# USER.net
KiCad netlist of a schematic drawn in EAGLE
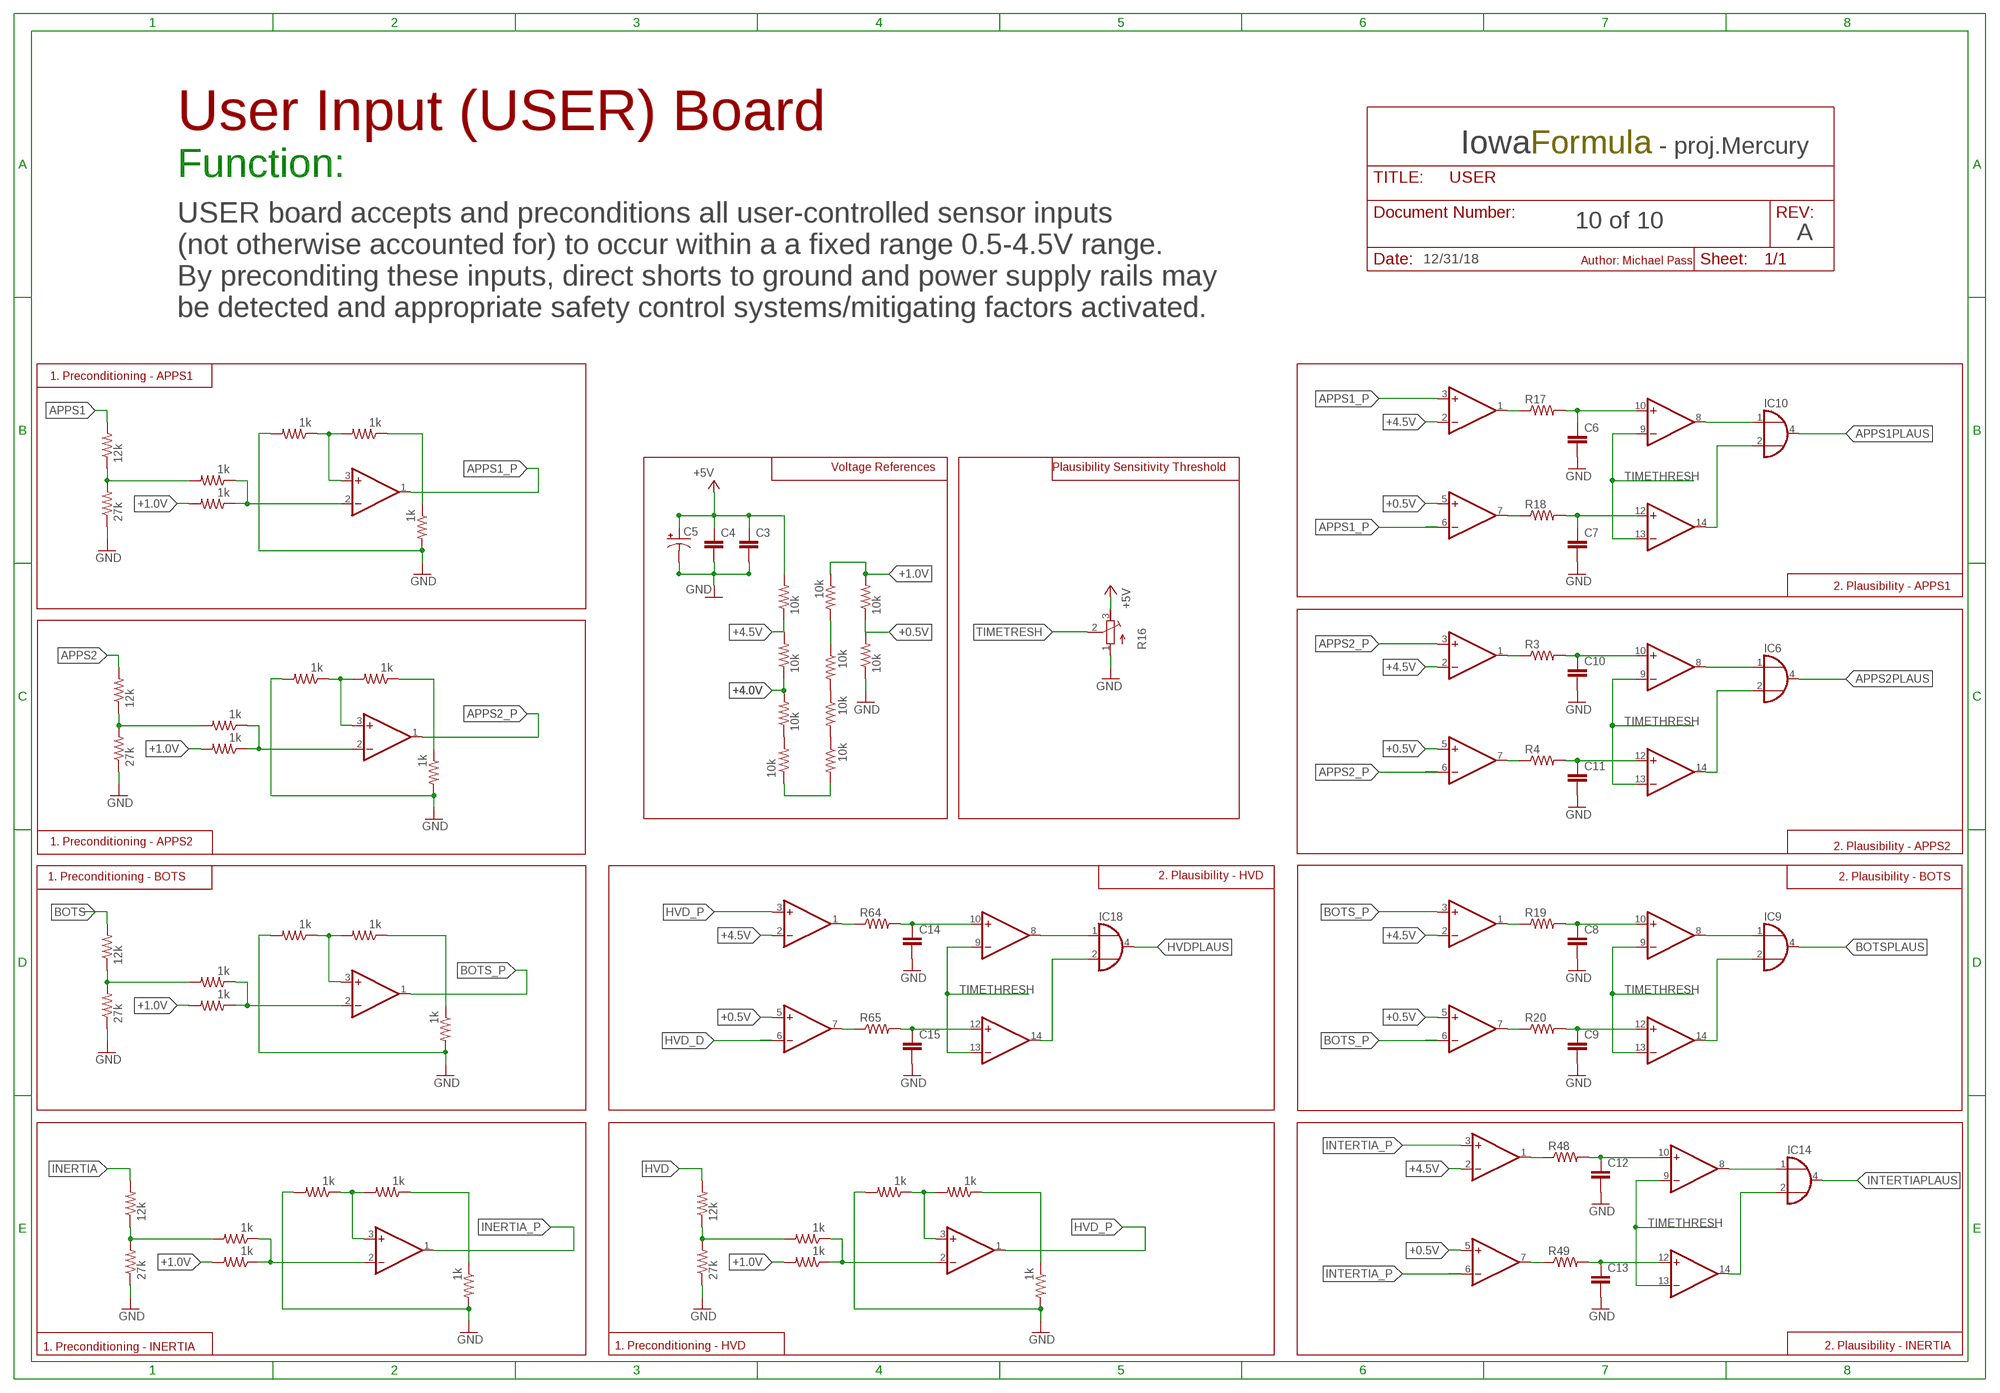
[diagram p0: schematic, sheet 1]

(export (version "E")
  (design (tool "Eeschema 10.0.6"))
  (components
    (comp (ref "C3")
      (value "C-EUC0805")
      (footprint "eagle-import:C0805")
      (libsource (lib "eagle-import") (part "C-EUC0805"))
    )
    (comp (ref "C4")
      (value "C-EUC0805")
      (footprint "eagle-import:C0805")
      (libsource (lib "eagle-import") (part "C-EUC0805"))
    )
    (comp (ref "C5")
      (value "CPOL-US085CS-1AR")
      (footprint "eagle-import:085CS_1AR")
      (libsource (lib "eagle-import") (part "CPOL-US085CS-1AR"))
    )
    (comp (ref "C6")
      (value "C-EUC0805")
      (footprint "eagle-import:C0805")
      (libsource (lib "eagle-import") (part "C-EUC0805"))
    )
    (comp (ref "C7")
      (value "C-EUC0805")
      (footprint "eagle-import:C0805")
      (libsource (lib "eagle-import") (part "C-EUC0805"))
    )
    (comp (ref "C8")
      (value "C-EUC0805")
      (footprint "eagle-import:C0805")
      (libsource (lib "eagle-import") (part "C-EUC0805"))
    )
    (comp (ref "C9")
      (value "C-EUC0805")
      (footprint "eagle-import:C0805")
      (libsource (lib "eagle-import") (part "C-EUC0805"))
    )
    (comp (ref "C10")
      (value "C-EUC0805")
      (footprint "eagle-import:C0805")
      (libsource (lib "eagle-import") (part "C-EUC0805"))
    )
    (comp (ref "C11")
      (value "C-EUC0805")
      (footprint "eagle-import:C0805")
      (libsource (lib "eagle-import") (part "C-EUC0805"))
    )
    (comp (ref "C12")
      (value "C-EUC0805")
      (footprint "eagle-import:C0805")
      (libsource (lib "eagle-import") (part "C-EUC0805"))
    )
    (comp (ref "C13")
      (value "C-EUC0805")
      (footprint "eagle-import:C0805")
      (libsource (lib "eagle-import") (part "C-EUC0805"))
    )
    (comp (ref "C14")
      (value "C-EUC0805")
      (footprint "eagle-import:C0805")
      (libsource (lib "eagle-import") (part "C-EUC0805"))
    )
    (comp (ref "C15")
      (value "C-EUC0805")
      (footprint "eagle-import:C0805")
      (libsource (lib "eagle-import") (part "C-EUC0805"))
    )
    (comp (ref "IC1")
      (value "OP11D")
      (footprint "eagle-import:SO14")
      (libsource (lib "eagle-import") (part "OP11D"))
    )
    (comp (ref "IC3")
      (value "OP11D")
      (footprint "eagle-import:SO14")
      (libsource (lib "eagle-import") (part "OP11D"))
    )
    (comp (ref "IC4")
      (value "OP11D")
      (footprint "eagle-import:SO14")
      (libsource (lib "eagle-import") (part "OP11D"))
    )
    (comp (ref "IC5")
      (value "OP11D")
      (footprint "eagle-import:SO14")
      (libsource (lib "eagle-import") (part "OP11D"))
    )
    (comp (ref "IC6")
      (value "74AHC1G32DCK")
      (footprint "eagle-import:SC70-5")
      (libsource (lib "eagle-import") (part "741G32DCKAHC"))
    )
    (comp (ref "IC7")
      (value "OP11D")
      (footprint "eagle-import:SO14")
      (libsource (lib "eagle-import") (part "OP11D"))
    )
    (comp (ref "IC8")
      (value "OP11D")
      (footprint "eagle-import:SO14")
      (libsource (lib "eagle-import") (part "OP11D"))
    )
    (comp (ref "IC9")
      (value "74AHC1G32DCK")
      (footprint "eagle-import:SC70-5")
      (libsource (lib "eagle-import") (part "741G32DCKAHC"))
    )
    (comp (ref "IC10")
      (value "74AHC1G32DCK")
      (footprint "eagle-import:SC70-5")
      (libsource (lib "eagle-import") (part "741G32DCKAHC"))
    )
    (comp (ref "IC13")
      (value "OP11D")
      (footprint "eagle-import:SO14")
      (libsource (lib "eagle-import") (part "OP11D"))
    )
    (comp (ref "IC14")
      (value "74AHC1G32DCK")
      (footprint "eagle-import:SC70-5")
      (libsource (lib "eagle-import") (part "741G32DCKAHC"))
    )
    (comp (ref "IC17")
      (value "OP11D")
      (footprint "eagle-import:SO14")
      (libsource (lib "eagle-import") (part "OP11D"))
    )
    (comp (ref "IC18")
      (value "74AHC1G32DCK")
      (footprint "eagle-import:SC70-5")
      (libsource (lib "eagle-import") (part "741G32DCKAHC"))
    )
    (comp (ref "IC19")
      (value "OP11D")
      (footprint "eagle-import:SO14")
      (libsource (lib "eagle-import") (part "OP11D"))
    )
    (comp (ref "IC20")
      (value "OP11D")
      (footprint "eagle-import:SO14")
      (libsource (lib "eagle-import") (part "OP11D"))
    )
    (comp (ref "R1")
      (value "12k")
      (footprint "eagle-import:R0805")
      (libsource (lib "eagle-import") (part "R-US_R0805"))
    )
    (comp (ref "R2")
      (value "27k")
      (footprint "eagle-import:R0805")
      (libsource (lib "eagle-import") (part "R-US_R0805"))
    )
    (comp (ref "R3")
      (value "R-US_R0805")
      (footprint "eagle-import:R0805")
      (libsource (lib "eagle-import") (part "R-US_R0805"))
    )
    (comp (ref "R4")
      (value "R-US_R0805")
      (footprint "eagle-import:R0805")
      (libsource (lib "eagle-import") (part "R-US_R0805"))
    )
    (comp (ref "R5")
      (value "10k")
      (footprint "eagle-import:R0805")
      (libsource (lib "eagle-import") (part "R-US_R0805"))
    )
    (comp (ref "R6")
      (value "10k")
      (footprint "eagle-import:R0805")
      (libsource (lib "eagle-import") (part "R-US_R0805"))
    )
    (comp (ref "R7")
      (value "12k")
      (footprint "eagle-import:R0805")
      (libsource (lib "eagle-import") (part "R-US_R0805"))
    )
    (comp (ref "R8")
      (value "10k")
      (footprint "eagle-import:R0805")
      (libsource (lib "eagle-import") (part "R-US_R0805"))
    )
    (comp (ref "R9")
      (value "10k")
      (footprint "eagle-import:R0805")
      (libsource (lib "eagle-import") (part "R-US_R0805"))
    )
    (comp (ref "R10")
      (value "10k")
      (footprint "eagle-import:R0805")
      (libsource (lib "eagle-import") (part "R-US_R0805"))
    )
    (comp (ref "R11")
      (value "10k")
      (footprint "eagle-import:R0805")
      (libsource (lib "eagle-import") (part "R-US_R0805"))
    )
    (comp (ref "R12")
      (value "10k")
      (footprint "eagle-import:R0805")
      (libsource (lib "eagle-import") (part "R-US_R0805"))
    )
    (comp (ref "R13")
      (value "10k")
      (footprint "eagle-import:R0805")
      (libsource (lib "eagle-import") (part "R-US_R0805"))
    )
    (comp (ref "R14")
      (value "10k")
      (footprint "eagle-import:R0805")
      (libsource (lib "eagle-import") (part "R-US_R0805"))
    )
    (comp (ref "R15")
      (value "10k")
      (footprint "eagle-import:R0805")
      (libsource (lib "eagle-import") (part "R-US_R0805"))
    )
    (comp (ref "R16")
      (value "R-TRIMM3224X")
      (footprint "eagle-import:RTRIM3224X")
      (libsource (lib "eagle-import") (part "R-TRIMM3224X"))
    )
    (comp (ref "R17")
      (value "R-US_R0805")
      (footprint "eagle-import:R0805")
      (libsource (lib "eagle-import") (part "R-US_R0805"))
    )
    (comp (ref "R18")
      (value "R-US_R0805")
      (footprint "eagle-import:R0805")
      (libsource (lib "eagle-import") (part "R-US_R0805"))
    )
    (comp (ref "R19")
      (value "R-US_R0805")
      (footprint "eagle-import:R0805")
      (libsource (lib "eagle-import") (part "R-US_R0805"))
    )
    (comp (ref "R20")
      (value "R-US_R0805")
      (footprint "eagle-import:R0805")
      (libsource (lib "eagle-import") (part "R-US_R0805"))
    )
    (comp (ref "R21")
      (value "27k")
      (footprint "eagle-import:R0805")
      (libsource (lib "eagle-import") (part "R-US_R0805"))
    )
    (comp (ref "R22")
      (value "1k")
      (footprint "eagle-import:R0805")
      (libsource (lib "eagle-import") (part "R-US_R0805"))
    )
    (comp (ref "R23")
      (value "1k")
      (footprint "eagle-import:R0805")
      (libsource (lib "eagle-import") (part "R-US_R0805"))
    )
    (comp (ref "R24")
      (value "1k")
      (footprint "eagle-import:R0805")
      (libsource (lib "eagle-import") (part "R-US_R0805"))
    )
    (comp (ref "R25")
      (value "1k")
      (footprint "eagle-import:R0805")
      (libsource (lib "eagle-import") (part "R-US_R0805"))
    )
    (comp (ref "R26")
      (value "1k")
      (footprint "eagle-import:R0805")
      (libsource (lib "eagle-import") (part "R-US_R0805"))
    )
    (comp (ref "R48")
      (value "R-US_R0805")
      (footprint "eagle-import:R0805")
      (libsource (lib "eagle-import") (part "R-US_R0805"))
    )
    (comp (ref "R49")
      (value "R-US_R0805")
      (footprint "eagle-import:R0805")
      (libsource (lib "eagle-import") (part "R-US_R0805"))
    )
    (comp (ref "R64")
      (value "R-US_R0805")
      (footprint "eagle-import:R0805")
      (libsource (lib "eagle-import") (part "R-US_R0805"))
    )
    (comp (ref "R65")
      (value "R-US_R0805")
      (footprint "eagle-import:R0805")
      (libsource (lib "eagle-import") (part "R-US_R0805"))
    )
    (comp (ref "R66")
      (value "1k")
      (footprint "eagle-import:R0805")
      (libsource (lib "eagle-import") (part "R-US_R0805"))
    )
    (comp (ref "R67")
      (value "1k")
      (footprint "eagle-import:R0805")
      (libsource (lib "eagle-import") (part "R-US_R0805"))
    )
    (comp (ref "R68")
      (value "1k")
      (footprint "eagle-import:R0805")
      (libsource (lib "eagle-import") (part "R-US_R0805"))
    )
    (comp (ref "R69")
      (value "1k")
      (footprint "eagle-import:R0805")
      (libsource (lib "eagle-import") (part "R-US_R0805"))
    )
    (comp (ref "R70")
      (value "1k")
      (footprint "eagle-import:R0805")
      (libsource (lib "eagle-import") (part "R-US_R0805"))
    )
    (comp (ref "R71")
      (value "12k")
      (footprint "eagle-import:R0805")
      (libsource (lib "eagle-import") (part "R-US_R0805"))
    )
    (comp (ref "R72")
      (value "27k")
      (footprint "eagle-import:R0805")
      (libsource (lib "eagle-import") (part "R-US_R0805"))
    )
    (comp (ref "R73")
      (value "1k")
      (footprint "eagle-import:R0805")
      (libsource (lib "eagle-import") (part "R-US_R0805"))
    )
    (comp (ref "R74")
      (value "1k")
      (footprint "eagle-import:R0805")
      (libsource (lib "eagle-import") (part "R-US_R0805"))
    )
    (comp (ref "R75")
      (value "1k")
      (footprint "eagle-import:R0805")
      (libsource (lib "eagle-import") (part "R-US_R0805"))
    )
    (comp (ref "R76")
      (value "1k")
      (footprint "eagle-import:R0805")
      (libsource (lib "eagle-import") (part "R-US_R0805"))
    )
    (comp (ref "R77")
      (value "1k")
      (footprint "eagle-import:R0805")
      (libsource (lib "eagle-import") (part "R-US_R0805"))
    )
    (comp (ref "R78")
      (value "12k")
      (footprint "eagle-import:R0805")
      (libsource (lib "eagle-import") (part "R-US_R0805"))
    )
    (comp (ref "R79")
      (value "27k")
      (footprint "eagle-import:R0805")
      (libsource (lib "eagle-import") (part "R-US_R0805"))
    )
    (comp (ref "R80")
      (value "1k")
      (footprint "eagle-import:R0805")
      (libsource (lib "eagle-import") (part "R-US_R0805"))
    )
    (comp (ref "R81")
      (value "1k")
      (footprint "eagle-import:R0805")
      (libsource (lib "eagle-import") (part "R-US_R0805"))
    )
    (comp (ref "R82")
      (value "1k")
      (footprint "eagle-import:R0805")
      (libsource (lib "eagle-import") (part "R-US_R0805"))
    )
    (comp (ref "R83")
      (value "1k")
      (footprint "eagle-import:R0805")
      (libsource (lib "eagle-import") (part "R-US_R0805"))
    )
    (comp (ref "R84")
      (value "1k")
      (footprint "eagle-import:R0805")
      (libsource (lib "eagle-import") (part "R-US_R0805"))
    )
    (comp (ref "R85")
      (value "12k")
      (footprint "eagle-import:R0805")
      (libsource (lib "eagle-import") (part "R-US_R0805"))
    )
    (comp (ref "R86")
      (value "27k")
      (footprint "eagle-import:R0805")
      (libsource (lib "eagle-import") (part "R-US_R0805"))
    )
    (comp (ref "R87")
      (value "1k")
      (footprint "eagle-import:R0805")
      (libsource (lib "eagle-import") (part "R-US_R0805"))
    )
    (comp (ref "R88")
      (value "1k")
      (footprint "eagle-import:R0805")
      (libsource (lib "eagle-import") (part "R-US_R0805"))
    )
    (comp (ref "R89")
      (value "1k")
      (footprint "eagle-import:R0805")
      (libsource (lib "eagle-import") (part "R-US_R0805"))
    )
    (comp (ref "R90")
      (value "1k")
      (footprint "eagle-import:R0805")
      (libsource (lib "eagle-import") (part "R-US_R0805"))
    )
    (comp (ref "R91")
      (value "1k")
      (footprint "eagle-import:R0805")
      (libsource (lib "eagle-import") (part "R-US_R0805"))
    )
  )
  (nets
    (net (code "1") (name "+0.5V") (class "Default")
      (node (ref "IC1") (pin "5") (pinfunction "+IN_5") (pintype "input"))
      (node (ref "IC13") (pin "5") (pinfunction "+IN_5") (pintype "input"))
      (node (ref "IC17") (pin "5") (pinfunction "+IN_5") (pintype "input"))
      (node (ref "IC4") (pin "5") (pinfunction "+IN_5") (pintype "input"))
      (node (ref "IC5") (pin "5") (pinfunction "+IN_5") (pintype "input"))
      (node (ref "R14") (pin "1") (pinfunction "1_1") (pintype "passive"))
      (node (ref "R15") (pin "2") (pinfunction "2_2") (pintype "passive"))
    )
    (net (code "2") (name "+1.0V") (class "Default")
      (node (ref "R13") (pin "1") (pinfunction "1_1") (pintype "passive"))
      (node (ref "R14") (pin "2") (pinfunction "2_2") (pintype "passive"))
      (node (ref "R23") (pin "2") (pinfunction "2_2") (pintype "passive"))
      (node (ref "R67") (pin "2") (pinfunction "2_2") (pintype "passive"))
      (node (ref "R74") (pin "2") (pinfunction "2_2") (pintype "passive"))
      (node (ref "R81") (pin "2") (pinfunction "2_2") (pintype "passive"))
      (node (ref "R88") (pin "2") (pinfunction "2_2") (pintype "passive"))
    )
    (net (code "3") (name "+4.0V") (class "Default")
      (node (ref "R6") (pin "1") (pinfunction "1_1") (pintype "passive"))
      (node (ref "R8") (pin "2") (pinfunction "2_2") (pintype "passive"))
    )
    (net (code "4") (name "+4.5V") (class "Default")
      (node (ref "IC1") (pin "2") (pinfunction "-IN_2") (pintype "input"))
      (node (ref "IC13") (pin "2") (pinfunction "-IN_2") (pintype "input"))
      (node (ref "IC17") (pin "2") (pinfunction "-IN_2") (pintype "input"))
      (node (ref "IC4") (pin "2") (pinfunction "-IN_2") (pintype "input"))
      (node (ref "IC5") (pin "2") (pinfunction "-IN_2") (pintype "input"))
      (node (ref "R5") (pin "1") (pinfunction "1_1") (pintype "passive"))
      (node (ref "R6") (pin "2") (pinfunction "2_2") (pintype "passive"))
    )
    (net (code "5") (name "+5V") (class "Default")
      (node (ref "C3") (pin "1") (pinfunction "1_1") (pintype "passive"))
      (node (ref "C4") (pin "1") (pinfunction "1_1") (pintype "passive"))
      (node (ref "C5") (pin "+") (pinfunction "+_+") (pintype "passive"))
      (node (ref "R16") (pin "3") (pinfunction "E_3") (pintype "passive"))
      (node (ref "R5") (pin "2") (pinfunction "2_2") (pintype "passive"))
    )
    (net (code "6") (name "/TIMETHRESH") (class "Default")
      (node (ref "IC1") (pin "13") (pinfunction "-IN_13") (pintype "input"))
      (node (ref "IC1") (pin "9") (pinfunction "-IN_9") (pintype "input"))
      (node (ref "IC13") (pin "13") (pinfunction "-IN_13") (pintype "input"))
      (node (ref "IC13") (pin "9") (pinfunction "-IN_9") (pintype "input"))
      (node (ref "IC17") (pin "13") (pinfunction "-IN_13") (pintype "input"))
      (node (ref "IC17") (pin "9") (pinfunction "-IN_9") (pintype "input"))
      (node (ref "IC4") (pin "13") (pinfunction "-IN_13") (pintype "input"))
      (node (ref "IC4") (pin "9") (pinfunction "-IN_9") (pintype "input"))
      (node (ref "IC5") (pin "13") (pinfunction "-IN_13") (pintype "input"))
      (node (ref "IC5") (pin "9") (pinfunction "-IN_9") (pintype "input"))
    )
    (net (code "7") (name "APPS1") (class "Default")
      (node (ref "R71") (pin "2") (pinfunction "2_2") (pintype "passive"))
    )
    (net (code "8") (name "APPS1PLAUS") (class "Default")
      (node (ref "IC10") (pin "4") (pinfunction "O_4") (pintype "output"))
    )
    (net (code "9") (name "APPS1_P") (class "Default")
      (node (ref "IC5") (pin "3") (pinfunction "+IN_3") (pintype "input"))
      (node (ref "IC5") (pin "6") (pinfunction "-IN_6") (pintype "input"))
      (node (ref "IC7") (pin "1") (pinfunction "OUT_1") (pintype "output"))
    )
    (net (code "10") (name "APPS2") (class "Default")
      (node (ref "R78") (pin "2") (pinfunction "2_2") (pintype "passive"))
    )
    (net (code "11") (name "APPS2PLAUS") (class "Default")
      (node (ref "IC6") (pin "4") (pinfunction "O_4") (pintype "output"))
    )
    (net (code "12") (name "APPS2_P") (class "Default")
      (node (ref "IC1") (pin "3") (pinfunction "+IN_3") (pintype "input"))
      (node (ref "IC1") (pin "6") (pinfunction "-IN_6") (pintype "input"))
      (node (ref "IC19") (pin "1") (pinfunction "OUT_1") (pintype "output"))
    )
    (net (code "13") (name "BOTS") (class "Default")
      (node (ref "R7") (pin "2") (pinfunction "2_2") (pintype "passive"))
    )
    (net (code "14") (name "BOTSPLAUS") (class "Default")
      (node (ref "IC9") (pin "4") (pinfunction "O_4") (pintype "output"))
    )
    (net (code "15") (name "BOTS_P") (class "Default")
      (node (ref "IC4") (pin "3") (pinfunction "+IN_3") (pintype "input"))
      (node (ref "IC4") (pin "6") (pinfunction "-IN_6") (pintype "input"))
      (node (ref "IC8") (pin "1") (pinfunction "OUT_1") (pintype "output"))
    )
    (net (code "16") (name "GND") (class "Default")
      (node (ref "C10") (pin "2") (pinfunction "2_2") (pintype "passive"))
      (node (ref "C11") (pin "2") (pinfunction "2_2") (pintype "passive"))
      (node (ref "C12") (pin "2") (pinfunction "2_2") (pintype "passive"))
      (node (ref "C13") (pin "2") (pinfunction "2_2") (pintype "passive"))
      (node (ref "C14") (pin "2") (pinfunction "2_2") (pintype "passive"))
      (node (ref "C15") (pin "2") (pinfunction "2_2") (pintype "passive"))
      (node (ref "C3") (pin "2") (pinfunction "2_2") (pintype "passive"))
      (node (ref "C4") (pin "2") (pinfunction "2_2") (pintype "passive"))
      (node (ref "C5") (pin "-") (pinfunction "-_-") (pintype "passive"))
      (node (ref "C6") (pin "2") (pinfunction "2_2") (pintype "passive"))
      (node (ref "C7") (pin "2") (pinfunction "2_2") (pintype "passive"))
      (node (ref "C8") (pin "2") (pinfunction "2_2") (pintype "passive"))
      (node (ref "C9") (pin "2") (pinfunction "2_2") (pintype "passive"))
      (node (ref "R15") (pin "1") (pinfunction "1_1") (pintype "passive"))
      (node (ref "R16") (pin "1") (pinfunction "A_1") (pintype "passive"))
      (node (ref "R2") (pin "1") (pinfunction "1_1") (pintype "passive"))
      (node (ref "R21") (pin "1") (pinfunction "1_1") (pintype "passive"))
      (node (ref "R24") (pin "2") (pinfunction "2_2") (pintype "passive"))
      (node (ref "R26") (pin "2") (pinfunction "2_2") (pintype "passive"))
      (node (ref "R68") (pin "2") (pinfunction "2_2") (pintype "passive"))
      (node (ref "R70") (pin "2") (pinfunction "2_2") (pintype "passive"))
      (node (ref "R72") (pin "1") (pinfunction "1_1") (pintype "passive"))
      (node (ref "R75") (pin "2") (pinfunction "2_2") (pintype "passive"))
      (node (ref "R77") (pin "2") (pinfunction "2_2") (pintype "passive"))
      (node (ref "R79") (pin "1") (pinfunction "1_1") (pintype "passive"))
      (node (ref "R82") (pin "2") (pinfunction "2_2") (pintype "passive"))
      (node (ref "R84") (pin "2") (pinfunction "2_2") (pintype "passive"))
      (node (ref "R86") (pin "1") (pinfunction "1_1") (pintype "passive"))
      (node (ref "R89") (pin "2") (pinfunction "2_2") (pintype "passive"))
      (node (ref "R91") (pin "2") (pinfunction "2_2") (pintype "passive"))
    )
    (net (code "17") (name "HVD") (class "Default")
      (node (ref "R85") (pin "2") (pinfunction "2_2") (pintype "passive"))
    )
    (net (code "18") (name "HVDPLAUS") (class "Default")
      (node (ref "IC18") (pin "4") (pinfunction "O_4") (pintype "output"))
    )
    (net (code "19") (name "HVD_D") (class "Default")
      (node (ref "IC17") (pin "6") (pinfunction "-IN_6") (pintype "input"))
    )
    (net (code "20") (name "HVD_P") (class "Default")
      (node (ref "IC17") (pin "3") (pinfunction "+IN_3") (pintype "input"))
      (node (ref "IC20") (pin "1") (pinfunction "OUT_1") (pintype "output"))
    )
    (net (code "21") (name "INERTIA") (class "Default")
      (node (ref "R1") (pin "2") (pinfunction "2_2") (pintype "passive"))
    )
    (net (code "22") (name "INERTIA_P") (class "Default")
      (node (ref "IC3") (pin "1") (pinfunction "OUT_1") (pintype "output"))
    )
    (net (code "23") (name "INTERTIAPLAUS") (class "Default")
      (node (ref "IC14") (pin "4") (pinfunction "O_4") (pintype "output"))
    )
    (net (code "24") (name "INTERTIA_P") (class "Default")
      (node (ref "IC13") (pin "3") (pinfunction "+IN_3") (pintype "input"))
      (node (ref "IC13") (pin "6") (pinfunction "-IN_6") (pintype "input"))
    )
    (net (code "25") (name "Net-(IC1A-OUT)") (class "Default")
      (node (ref "IC1") (pin "1") (pinfunction "OUT_1") (pintype "output"))
      (node (ref "R3") (pin "1") (pinfunction "1_1") (pintype "passive"))
    )
    (net (code "26") (name "Net-(IC1B-OUT)") (class "Default")
      (node (ref "IC1") (pin "7") (pinfunction "OUT_7") (pintype "output"))
      (node (ref "R4") (pin "1") (pinfunction "1_1") (pintype "passive"))
    )
    (net (code "27") (name "Net-(IC1C-+IN)") (class "Default")
      (node (ref "C10") (pin "1") (pinfunction "1_1") (pintype "passive"))
      (node (ref "IC1") (pin "10") (pinfunction "+IN_10") (pintype "input"))
      (node (ref "R3") (pin "2") (pinfunction "2_2") (pintype "passive"))
    )
    (net (code "28") (name "Net-(IC1C-OUT)") (class "Default")
      (node (ref "IC1") (pin "8") (pinfunction "OUT_8") (pintype "output"))
      (node (ref "IC6") (pin "1") (pinfunction "I0_1") (pintype "input"))
    )
    (net (code "29") (name "Net-(IC1D-+IN)") (class "Default")
      (node (ref "C11") (pin "1") (pinfunction "1_1") (pintype "passive"))
      (node (ref "IC1") (pin "12") (pinfunction "+IN_12") (pintype "input"))
      (node (ref "R4") (pin "2") (pinfunction "2_2") (pintype "passive"))
    )
    (net (code "30") (name "Net-(IC1D-OUT)") (class "Default")
      (node (ref "IC1") (pin "14") (pinfunction "OUT_14") (pintype "output"))
      (node (ref "IC6") (pin "2") (pinfunction "I1_2") (pintype "input"))
    )
    (net (code "31") (name "Net-(IC3A-+IN)") (class "Default")
      (node (ref "IC3") (pin "3") (pinfunction "+IN_3") (pintype "input"))
      (node (ref "R68") (pin "1") (pinfunction "1_1") (pintype "passive"))
      (node (ref "R69") (pin "2") (pinfunction "2_2") (pintype "passive"))
    )
    (net (code "32") (name "Net-(IC3A--IN)") (class "Default")
      (node (ref "IC3") (pin "2") (pinfunction "-IN_2") (pintype "input"))
      (node (ref "R66") (pin "1") (pinfunction "1_1") (pintype "passive"))
      (node (ref "R67") (pin "1") (pinfunction "1_1") (pintype "passive"))
    )
    (net (code "33") (name "Net-(IC4A-OUT)") (class "Default")
      (node (ref "IC4") (pin "1") (pinfunction "OUT_1") (pintype "output"))
      (node (ref "R19") (pin "1") (pinfunction "1_1") (pintype "passive"))
    )
    (net (code "34") (name "Net-(IC4B-OUT)") (class "Default")
      (node (ref "IC4") (pin "7") (pinfunction "OUT_7") (pintype "output"))
      (node (ref "R20") (pin "1") (pinfunction "1_1") (pintype "passive"))
    )
    (net (code "35") (name "Net-(IC4C-+IN)") (class "Default")
      (node (ref "C8") (pin "1") (pinfunction "1_1") (pintype "passive"))
      (node (ref "IC4") (pin "10") (pinfunction "+IN_10") (pintype "input"))
      (node (ref "R19") (pin "2") (pinfunction "2_2") (pintype "passive"))
    )
    (net (code "36") (name "Net-(IC4C-OUT)") (class "Default")
      (node (ref "IC4") (pin "8") (pinfunction "OUT_8") (pintype "output"))
      (node (ref "IC9") (pin "1") (pinfunction "I0_1") (pintype "input"))
    )
    (net (code "37") (name "Net-(IC4D-+IN)") (class "Default")
      (node (ref "C9") (pin "1") (pinfunction "1_1") (pintype "passive"))
      (node (ref "IC4") (pin "12") (pinfunction "+IN_12") (pintype "input"))
      (node (ref "R20") (pin "2") (pinfunction "2_2") (pintype "passive"))
    )
    (net (code "38") (name "Net-(IC4D-OUT)") (class "Default")
      (node (ref "IC4") (pin "14") (pinfunction "OUT_14") (pintype "output"))
      (node (ref "IC9") (pin "2") (pinfunction "I1_2") (pintype "input"))
    )
    (net (code "39") (name "Net-(IC5A-OUT)") (class "Default")
      (node (ref "IC5") (pin "1") (pinfunction "OUT_1") (pintype "output"))
      (node (ref "R17") (pin "1") (pinfunction "1_1") (pintype "passive"))
    )
    (net (code "40") (name "Net-(IC5B-OUT)") (class "Default")
      (node (ref "IC5") (pin "7") (pinfunction "OUT_7") (pintype "output"))
      (node (ref "R18") (pin "1") (pinfunction "1_1") (pintype "passive"))
    )
    (net (code "41") (name "Net-(IC5C-+IN)") (class "Default")
      (node (ref "C6") (pin "1") (pinfunction "1_1") (pintype "passive"))
      (node (ref "IC5") (pin "10") (pinfunction "+IN_10") (pintype "input"))
      (node (ref "R17") (pin "2") (pinfunction "2_2") (pintype "passive"))
    )
    (net (code "42") (name "Net-(IC5D-+IN)") (class "Default")
      (node (ref "C7") (pin "1") (pinfunction "1_1") (pintype "passive"))
      (node (ref "IC5") (pin "12") (pinfunction "+IN_12") (pintype "input"))
      (node (ref "R18") (pin "2") (pinfunction "2_2") (pintype "passive"))
    )
    (net (code "43") (name "Net-(IC7A-+IN)") (class "Default")
      (node (ref "IC7") (pin "3") (pinfunction "+IN_3") (pintype "input"))
      (node (ref "R75") (pin "1") (pinfunction "1_1") (pintype "passive"))
      (node (ref "R76") (pin "2") (pinfunction "2_2") (pintype "passive"))
    )
    (net (code "44") (name "Net-(IC7A--IN)") (class "Default")
      (node (ref "IC7") (pin "2") (pinfunction "-IN_2") (pintype "input"))
      (node (ref "R73") (pin "1") (pinfunction "1_1") (pintype "passive"))
      (node (ref "R74") (pin "1") (pinfunction "1_1") (pintype "passive"))
    )
    (net (code "45") (name "Net-(IC8A-+IN)") (class "Default")
      (node (ref "IC8") (pin "3") (pinfunction "+IN_3") (pintype "input"))
      (node (ref "R24") (pin "1") (pinfunction "1_1") (pintype "passive"))
      (node (ref "R25") (pin "2") (pinfunction "2_2") (pintype "passive"))
    )
    (net (code "46") (name "Net-(IC8A--IN)") (class "Default")
      (node (ref "IC8") (pin "2") (pinfunction "-IN_2") (pintype "input"))
      (node (ref "R22") (pin "1") (pinfunction "1_1") (pintype "passive"))
      (node (ref "R23") (pin "1") (pinfunction "1_1") (pintype "passive"))
    )
    (net (code "47") (name "Net-(IC10A-I0)") (class "Default")
      (node (ref "IC10") (pin "1") (pinfunction "I0_1") (pintype "input"))
      (node (ref "IC5") (pin "8") (pinfunction "OUT_8") (pintype "output"))
    )
    (net (code "48") (name "Net-(IC10A-I1)") (class "Default")
      (node (ref "IC10") (pin "2") (pinfunction "I1_2") (pintype "input"))
      (node (ref "IC5") (pin "14") (pinfunction "OUT_14") (pintype "output"))
    )
    (net (code "49") (name "Net-(IC13A-OUT)") (class "Default")
      (node (ref "IC13") (pin "1") (pinfunction "OUT_1") (pintype "output"))
      (node (ref "R48") (pin "1") (pinfunction "1_1") (pintype "passive"))
    )
    (net (code "50") (name "Net-(IC13B-OUT)") (class "Default")
      (node (ref "IC13") (pin "7") (pinfunction "OUT_7") (pintype "output"))
      (node (ref "R49") (pin "1") (pinfunction "1_1") (pintype "passive"))
    )
    (net (code "51") (name "Net-(IC13C-+IN)") (class "Default")
      (node (ref "C12") (pin "1") (pinfunction "1_1") (pintype "passive"))
      (node (ref "IC13") (pin "10") (pinfunction "+IN_10") (pintype "input"))
      (node (ref "R48") (pin "2") (pinfunction "2_2") (pintype "passive"))
    )
    (net (code "52") (name "Net-(IC13C-OUT)") (class "Default")
      (node (ref "IC13") (pin "8") (pinfunction "OUT_8") (pintype "output"))
      (node (ref "IC14") (pin "1") (pinfunction "I0_1") (pintype "input"))
    )
    (net (code "53") (name "Net-(IC13D-+IN)") (class "Default")
      (node (ref "C13") (pin "1") (pinfunction "1_1") (pintype "passive"))
      (node (ref "IC13") (pin "12") (pinfunction "+IN_12") (pintype "input"))
      (node (ref "R49") (pin "2") (pinfunction "2_2") (pintype "passive"))
    )
    (net (code "54") (name "Net-(IC13D-OUT)") (class "Default")
      (node (ref "IC13") (pin "14") (pinfunction "OUT_14") (pintype "output"))
      (node (ref "IC14") (pin "2") (pinfunction "I1_2") (pintype "input"))
    )
    (net (code "55") (name "Net-(IC17A-OUT)") (class "Default")
      (node (ref "IC17") (pin "1") (pinfunction "OUT_1") (pintype "output"))
      (node (ref "R64") (pin "1") (pinfunction "1_1") (pintype "passive"))
    )
    (net (code "56") (name "Net-(IC17B-OUT)") (class "Default")
      (node (ref "IC17") (pin "7") (pinfunction "OUT_7") (pintype "output"))
      (node (ref "R65") (pin "1") (pinfunction "1_1") (pintype "passive"))
    )
    (net (code "57") (name "Net-(IC17C-+IN)") (class "Default")
      (node (ref "C14") (pin "1") (pinfunction "1_1") (pintype "passive"))
      (node (ref "IC17") (pin "10") (pinfunction "+IN_10") (pintype "input"))
      (node (ref "R64") (pin "2") (pinfunction "2_2") (pintype "passive"))
    )
    (net (code "58") (name "Net-(IC17C-OUT)") (class "Default")
      (node (ref "IC17") (pin "8") (pinfunction "OUT_8") (pintype "output"))
      (node (ref "IC18") (pin "1") (pinfunction "I0_1") (pintype "input"))
    )
    (net (code "59") (name "Net-(IC17D-+IN)") (class "Default")
      (node (ref "C15") (pin "1") (pinfunction "1_1") (pintype "passive"))
      (node (ref "IC17") (pin "12") (pinfunction "+IN_12") (pintype "input"))
      (node (ref "R65") (pin "2") (pinfunction "2_2") (pintype "passive"))
    )
    (net (code "60") (name "Net-(IC17D-OUT)") (class "Default")
      (node (ref "IC17") (pin "14") (pinfunction "OUT_14") (pintype "output"))
      (node (ref "IC18") (pin "2") (pinfunction "I1_2") (pintype "input"))
    )
    (net (code "61") (name "Net-(IC19A-+IN)") (class "Default")
      (node (ref "IC19") (pin "3") (pinfunction "+IN_3") (pintype "input"))
      (node (ref "R82") (pin "1") (pinfunction "1_1") (pintype "passive"))
      (node (ref "R83") (pin "2") (pinfunction "2_2") (pintype "passive"))
    )
    (net (code "62") (name "Net-(IC19A--IN)") (class "Default")
      (node (ref "IC19") (pin "2") (pinfunction "-IN_2") (pintype "input"))
      (node (ref "R80") (pin "1") (pinfunction "1_1") (pintype "passive"))
      (node (ref "R81") (pin "1") (pinfunction "1_1") (pintype "passive"))
    )
    (net (code "63") (name "Net-(IC20A-+IN)") (class "Default")
      (node (ref "IC20") (pin "3") (pinfunction "+IN_3") (pintype "input"))
      (node (ref "R89") (pin "1") (pinfunction "1_1") (pintype "passive"))
      (node (ref "R90") (pin "2") (pinfunction "2_2") (pintype "passive"))
    )
    (net (code "64") (name "Net-(IC20A--IN)") (class "Default")
      (node (ref "IC20") (pin "2") (pinfunction "-IN_2") (pintype "input"))
      (node (ref "R87") (pin "1") (pinfunction "1_1") (pintype "passive"))
      (node (ref "R88") (pin "1") (pinfunction "1_1") (pintype "passive"))
    )
    (net (code "65") (name "Net-(R1-Pad1)") (class "Default")
      (node (ref "R1") (pin "1") (pinfunction "1_1") (pintype "passive"))
      (node (ref "R2") (pin "2") (pinfunction "2_2") (pintype "passive"))
      (node (ref "R66") (pin "2") (pinfunction "2_2") (pintype "passive"))
    )
    (net (code "66") (name "Net-(R8-Pad1)") (class "Default")
      (node (ref "R8") (pin "1") (pinfunction "1_1") (pintype "passive"))
      (node (ref "R9") (pin "2") (pinfunction "2_2") (pintype "passive"))
    )
    (net (code "67") (name "Net-(R10-Pad1)") (class "Default")
      (node (ref "R10") (pin "1") (pinfunction "1_1") (pintype "passive"))
      (node (ref "R11") (pin "2") (pinfunction "2_2") (pintype "passive"))
    )
    (net (code "68") (name "Net-(R10-Pad2)") (class "Default")
      (node (ref "R10") (pin "2") (pinfunction "2_2") (pintype "passive"))
      (node (ref "R9") (pin "1") (pinfunction "1_1") (pintype "passive"))
    )
    (net (code "69") (name "Net-(R11-Pad1)") (class "Default")
      (node (ref "R11") (pin "1") (pinfunction "1_1") (pintype "passive"))
      (node (ref "R12") (pin "2") (pinfunction "2_2") (pintype "passive"))
    )
    (net (code "70") (name "Net-(R12-Pad1)") (class "Default")
      (node (ref "R12") (pin "1") (pinfunction "1_1") (pintype "passive"))
      (node (ref "R13") (pin "2") (pinfunction "2_2") (pintype "passive"))
    )
    (net (code "71") (name "Net-(R21-Pad2)") (class "Default")
      (node (ref "R21") (pin "2") (pinfunction "2_2") (pintype "passive"))
      (node (ref "R22") (pin "2") (pinfunction "2_2") (pintype "passive"))
      (node (ref "R7") (pin "1") (pinfunction "1_1") (pintype "passive"))
    )
    (net (code "72") (name "Net-(R25-Pad1)") (class "Default")
      (node (ref "R25") (pin "1") (pinfunction "1_1") (pintype "passive"))
      (node (ref "R26") (pin "1") (pinfunction "1_1") (pintype "passive"))
    )
    (net (code "73") (name "Net-(R69-Pad1)") (class "Default")
      (node (ref "R69") (pin "1") (pinfunction "1_1") (pintype "passive"))
      (node (ref "R70") (pin "1") (pinfunction "1_1") (pintype "passive"))
    )
    (net (code "74") (name "Net-(R71-Pad1)") (class "Default")
      (node (ref "R71") (pin "1") (pinfunction "1_1") (pintype "passive"))
      (node (ref "R72") (pin "2") (pinfunction "2_2") (pintype "passive"))
      (node (ref "R73") (pin "2") (pinfunction "2_2") (pintype "passive"))
    )
    (net (code "75") (name "Net-(R76-Pad1)") (class "Default")
      (node (ref "R76") (pin "1") (pinfunction "1_1") (pintype "passive"))
      (node (ref "R77") (pin "1") (pinfunction "1_1") (pintype "passive"))
    )
    (net (code "76") (name "Net-(R78-Pad1)") (class "Default")
      (node (ref "R78") (pin "1") (pinfunction "1_1") (pintype "passive"))
      (node (ref "R79") (pin "2") (pinfunction "2_2") (pintype "passive"))
      (node (ref "R80") (pin "2") (pinfunction "2_2") (pintype "passive"))
    )
    (net (code "77") (name "Net-(R83-Pad1)") (class "Default")
      (node (ref "R83") (pin "1") (pinfunction "1_1") (pintype "passive"))
      (node (ref "R84") (pin "1") (pinfunction "1_1") (pintype "passive"))
    )
    (net (code "78") (name "Net-(R85-Pad1)") (class "Default")
      (node (ref "R85") (pin "1") (pinfunction "1_1") (pintype "passive"))
      (node (ref "R86") (pin "2") (pinfunction "2_2") (pintype "passive"))
      (node (ref "R87") (pin "2") (pinfunction "2_2") (pintype "passive"))
    )
    (net (code "79") (name "Net-(R90-Pad1)") (class "Default")
      (node (ref "R90") (pin "1") (pinfunction "1_1") (pintype "passive"))
      (node (ref "R91") (pin "1") (pinfunction "1_1") (pintype "passive"))
    )
    (net (code "80") (name "TIMETRESH") (class "Default")
      (node (ref "R16") (pin "2") (pinfunction "S_2") (pintype "passive"))
    )
  )
)
